# QCopter.net
KiCad netlist of a schematic drawn in EAGLE
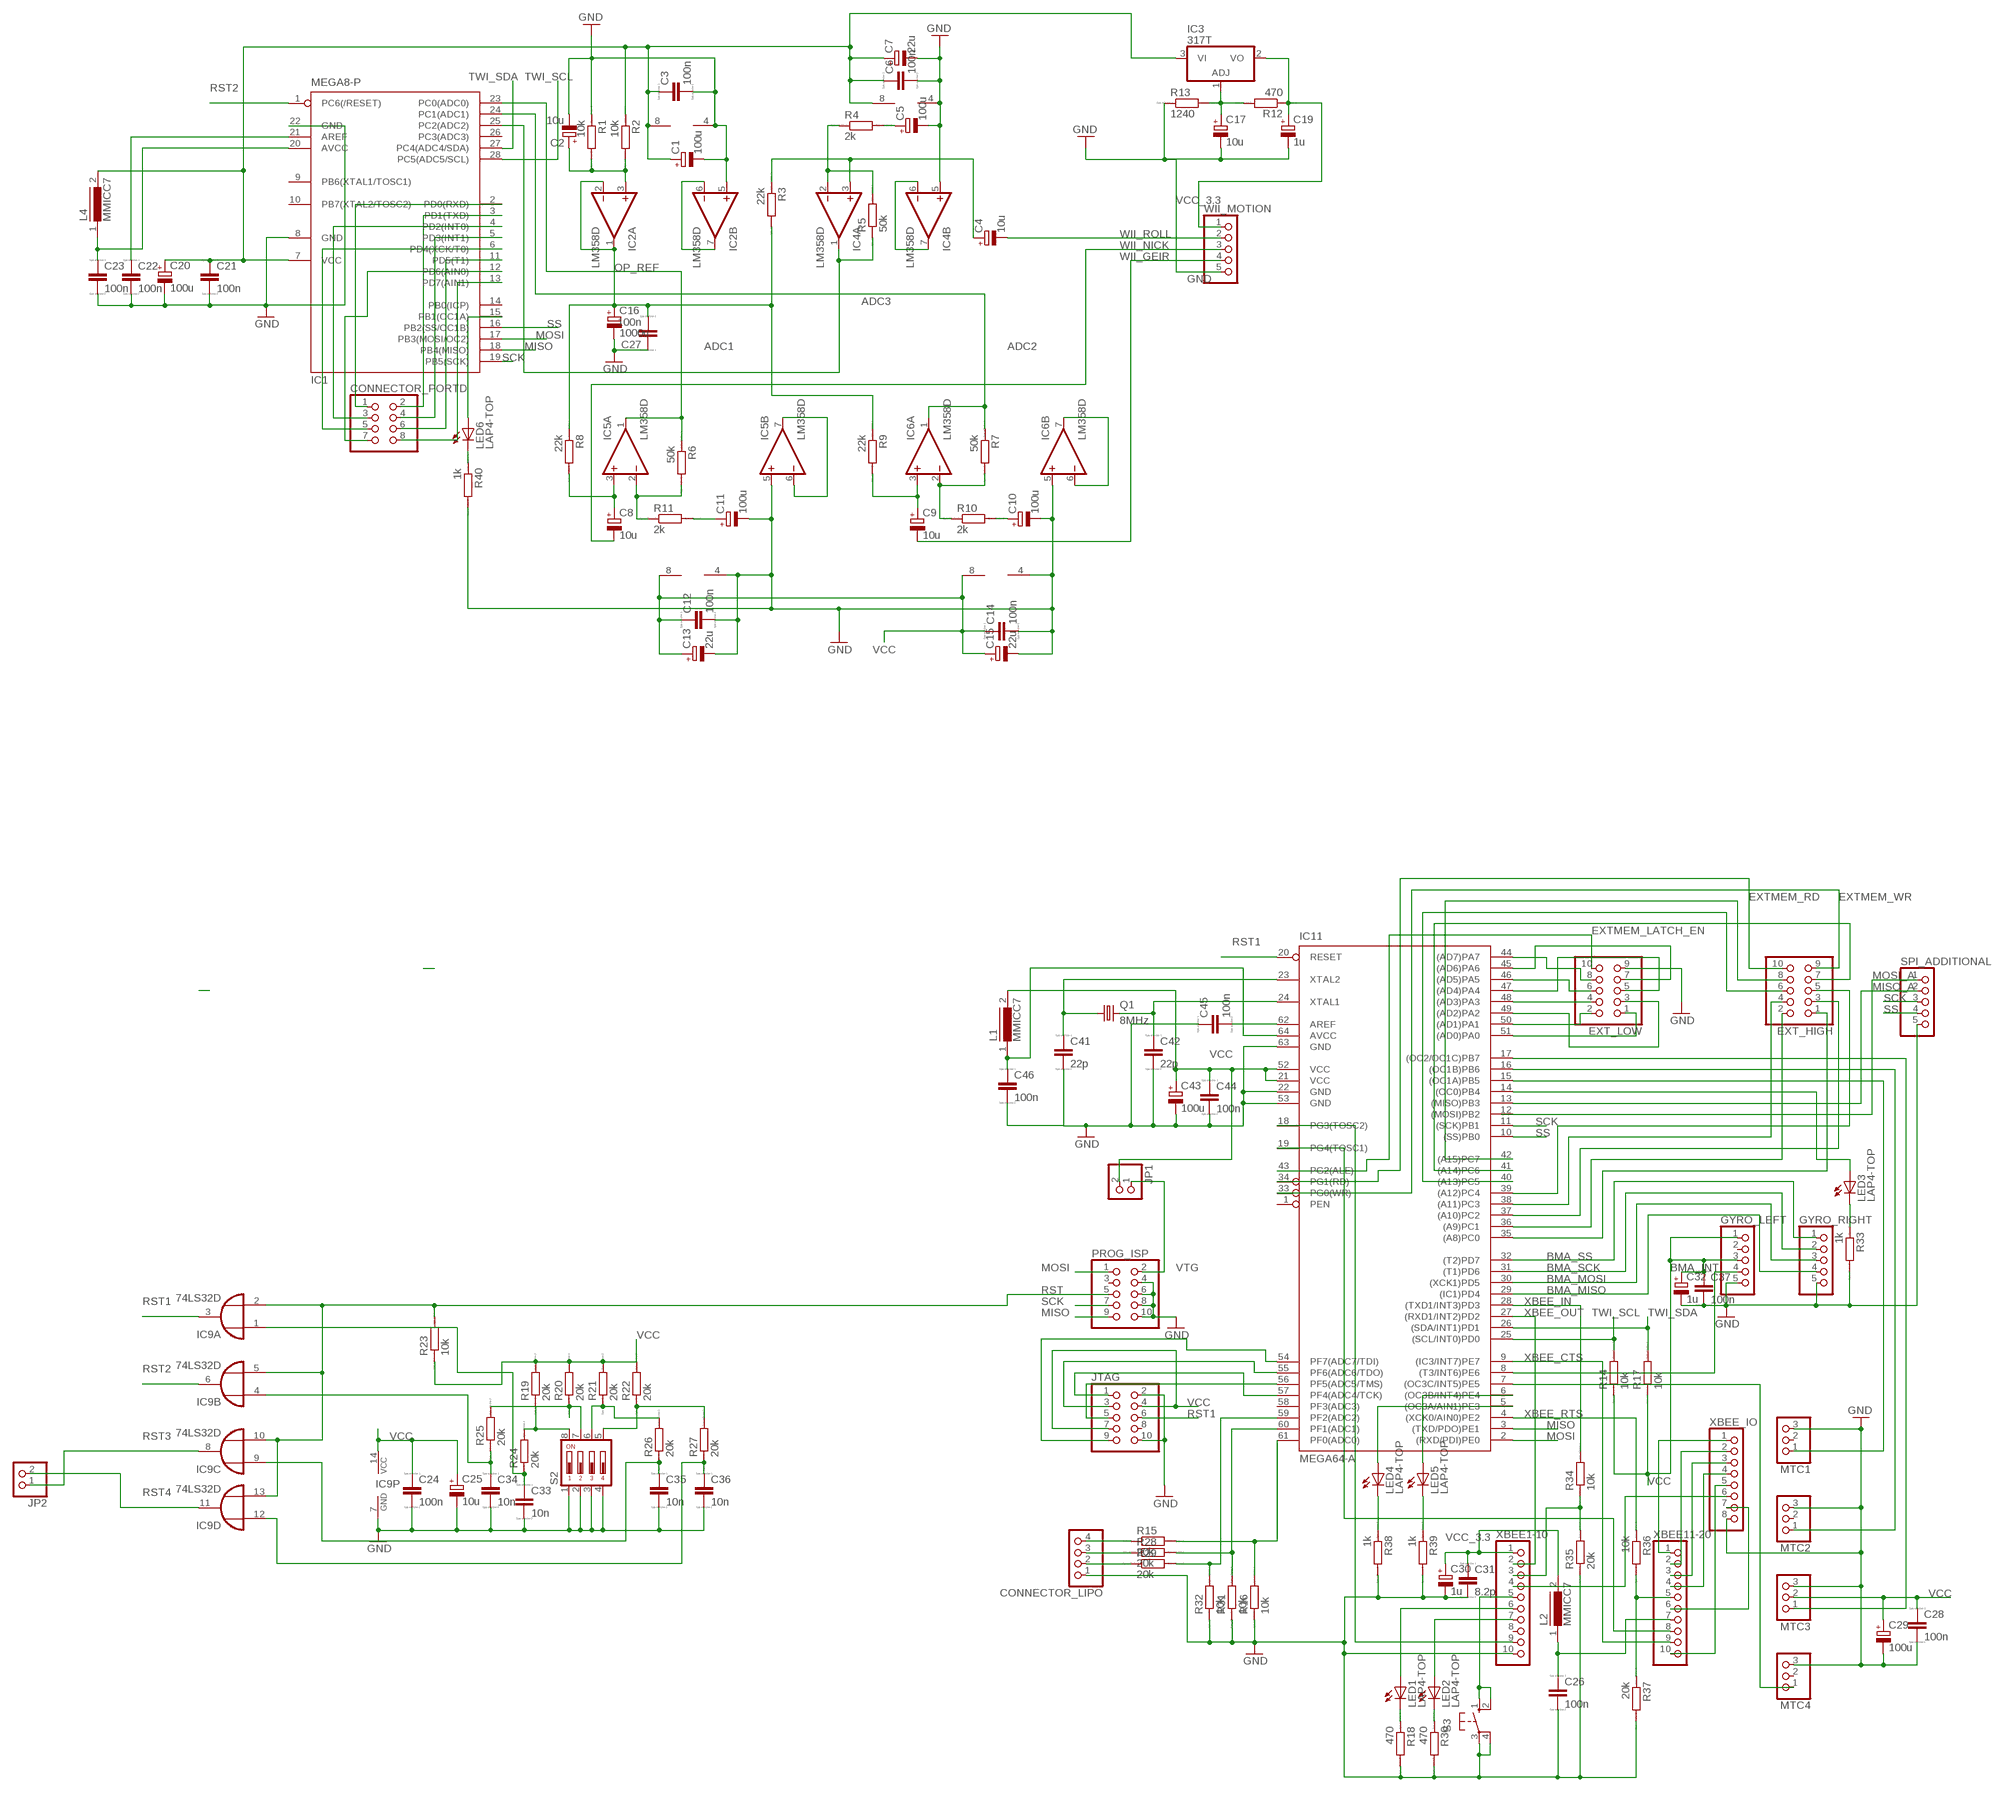
[diagram p0: schematic, sheet 1]

(export (version "E")
  (design (tool "Eeschema 10.0.6"))
  (components
    (comp (ref "C1")
      (value "100u")
      (footprint "eagle-import:153CLV-0505")
      (libsource (lib "eagle-import") (part "CPOL-EU153CLV-0505"))
    )
    (comp (ref "C2")
      (value "10u")
      (footprint "eagle-import:153CLV-0505")
      (libsource (lib "eagle-import") (part "CPOL-EU153CLV-0505"))
    )
    (comp (ref "C3")
      (value "100n")
      (footprint "eagle-import:C0805K")
      (libsource (lib "eagle-import") (part "C-EUC0805K"))
    )
    (comp (ref "C4")
      (value "10u")
      (footprint "eagle-import:153CLV-0505")
      (libsource (lib "eagle-import") (part "CPOL-EU153CLV-0505"))
    )
    (comp (ref "C5")
      (value "100u")
      (footprint "eagle-import:153CLV-0505")
      (libsource (lib "eagle-import") (part "CPOL-EU153CLV-0505"))
    )
    (comp (ref "C6")
      (value "100n")
      (footprint "eagle-import:C0805K")
      (libsource (lib "eagle-import") (part "C-EUC0805K"))
    )
    (comp (ref "C7")
      (value "22u")
      (footprint "eagle-import:153CLV-0505")
      (libsource (lib "eagle-import") (part "CPOL-EU153CLV-0505"))
    )
    (comp (ref "C8")
      (value "10u")
      (footprint "eagle-import:153CLV-0505")
      (libsource (lib "eagle-import") (part "CPOL-EU153CLV-0505"))
    )
    (comp (ref "C9")
      (value "10u")
      (footprint "eagle-import:153CLV-0505")
      (libsource (lib "eagle-import") (part "CPOL-EU153CLV-0505"))
    )
    (comp (ref "C10")
      (value "100u")
      (footprint "eagle-import:153CLV-0505")
      (libsource (lib "eagle-import") (part "CPOL-EU153CLV-0505"))
    )
    (comp (ref "C11")
      (value "100u")
      (footprint "eagle-import:153CLV-0505")
      (libsource (lib "eagle-import") (part "CPOL-EU153CLV-0505"))
    )
    (comp (ref "C12")
      (value "100n")
      (footprint "eagle-import:C0805K")
      (libsource (lib "eagle-import") (part "C-EUC0805K"))
    )
    (comp (ref "C13")
      (value "22u")
      (footprint "eagle-import:153CLV-0505")
      (libsource (lib "eagle-import") (part "CPOL-EU153CLV-0505"))
    )
    (comp (ref "C14")
      (value "100n")
      (footprint "eagle-import:C0805K")
      (libsource (lib "eagle-import") (part "C-EUC0805K"))
    )
    (comp (ref "C15")
      (value "22u")
      (footprint "eagle-import:153CLV-0505")
      (libsource (lib "eagle-import") (part "CPOL-EU153CLV-0505"))
    )
    (comp (ref "C16")
      (value "1000u")
      (footprint "eagle-import:E3,5-10")
      (libsource (lib "eagle-import") (part "CPOL-EUE3.5-10"))
    )
    (comp (ref "C17")
      (value "10u")
      (footprint "eagle-import:E5-6")
      (libsource (lib "eagle-import") (part "CPOL-EUE5-6"))
    )
    (comp (ref "C19")
      (value "1u")
      (footprint "eagle-import:E5-6")
      (libsource (lib "eagle-import") (part "CPOL-EUE5-6"))
    )
    (comp (ref "C20")
      (value "100u")
      (footprint "eagle-import:E5-6")
      (libsource (lib "eagle-import") (part "CPOL-EUE5-6"))
    )
    (comp (ref "C21")
      (value "100n")
      (footprint "eagle-import:C025-025X050")
      (libsource (lib "eagle-import") (part "C-EU025-025X050"))
    )
    (comp (ref "C22")
      (value "100n")
      (footprint "eagle-import:C025-025X050")
      (libsource (lib "eagle-import") (part "C-EU025-025X050"))
    )
    (comp (ref "C23")
      (value "100n")
      (footprint "eagle-import:C025-025X050")
      (libsource (lib "eagle-import") (part "C-EU025-025X050"))
    )
    (comp (ref "C24")
      (value "100n")
      (footprint "eagle-import:C0805K")
      (libsource (lib "eagle-import") (part "C-EUC0805K"))
    )
    (comp (ref "C25")
      (value "10u")
      (footprint "eagle-import:153CLV-0505")
      (libsource (lib "eagle-import") (part "CPOL-EU153CLV-0505"))
    )
    (comp (ref "C26")
      (value "100n")
      (footprint "eagle-import:C0805K")
      (libsource (lib "eagle-import") (part "C-EUC0805K"))
    )
    (comp (ref "C27")
      (value "100n")
      (footprint "eagle-import:C0805K")
      (libsource (lib "eagle-import") (part "C-EUC0805K"))
    )
    (comp (ref "C28")
      (value "100n")
      (footprint "eagle-import:C0805K")
      (libsource (lib "eagle-import") (part "C-EUC0805K"))
    )
    (comp (ref "C29")
      (value "100u")
      (footprint "eagle-import:153CLV-0605")
      (libsource (lib "eagle-import") (part "CPOL-EU153CLV-0605"))
    )
    (comp (ref "C30")
      (value "1u")
      (footprint "eagle-import:153CLV-0605")
      (libsource (lib "eagle-import") (part "CPOL-EU153CLV-0605"))
    )
    (comp (ref "C31")
      (value "8.2p")
      (footprint "eagle-import:C025-024X044")
      (libsource (lib "eagle-import") (part "C-EU025-024X044"))
    )
    (comp (ref "C32")
      (value "1u")
      (footprint "eagle-import:153CLV-0605")
      (libsource (lib "eagle-import") (part "CPOL-EU153CLV-0605"))
    )
    (comp (ref "C33")
      (value "10n")
      (footprint "eagle-import:C0805K")
      (libsource (lib "eagle-import") (part "C-EUC0805K"))
    )
    (comp (ref "C34")
      (value "10n")
      (footprint "eagle-import:C0805K")
      (libsource (lib "eagle-import") (part "C-EUC0805K"))
    )
    (comp (ref "C35")
      (value "10n")
      (footprint "eagle-import:C0805K")
      (libsource (lib "eagle-import") (part "C-EUC0805K"))
    )
    (comp (ref "C36")
      (value "10n")
      (footprint "eagle-import:C0805K")
      (libsource (lib "eagle-import") (part "C-EUC0805K"))
    )
    (comp (ref "C37")
      (value "100n")
      (footprint "eagle-import:C0805K")
      (libsource (lib "eagle-import") (part "C-EUC0805K"))
    )
    (comp (ref "C41")
      (value "22p")
      (footprint "eagle-import:C025-025X050")
      (libsource (lib "eagle-import") (part "C-EU025-025X050"))
    )
    (comp (ref "C42")
      (value "22p")
      (footprint "eagle-import:C025-025X050")
      (libsource (lib "eagle-import") (part "C-EU025-025X050"))
    )
    (comp (ref "C43")
      (value "100u")
      (footprint "eagle-import:153CLV-0605")
      (libsource (lib "eagle-import") (part "CPOL-EU153CLV-0605"))
    )
    (comp (ref "C44")
      (value "100n")
      (footprint "eagle-import:C0805K")
      (libsource (lib "eagle-import") (part "C-EUC0805K"))
    )
    (comp (ref "C45")
      (value "100n")
      (footprint "eagle-import:C0805K")
      (libsource (lib "eagle-import") (part "C-EUC0805K"))
    )
    (comp (ref "C46")
      (value "100n")
      (footprint "eagle-import:C0805K")
      (libsource (lib "eagle-import") (part "C-EUC0805K"))
    )
    (comp (ref "CONNECTOR_LIPO")
      (value "PINHD-1X4")
      (footprint "eagle-import:1X04")
      (libsource (lib "eagle-import") (part "PINHD-1X4"))
    )
    (comp (ref "CONNECTOR_PORTD")
      (value "PINHD-2X4")
      (footprint "eagle-import:2X04")
      (libsource (lib "eagle-import") (part "PINHD-2X4"))
    )
    (comp (ref "EXT_HIGH")
      (value "PINHD-2X5")
      (footprint "eagle-import:2X05")
      (libsource (lib "eagle-import") (part "PINHD-2X5"))
    )
    (comp (ref "EXT_LOW")
      (value "PINHD-2X5")
      (footprint "eagle-import:2X05")
      (libsource (lib "eagle-import") (part "PINHD-2X5"))
    )
    (comp (ref "GYRO_LEFT")
      (value "PINHD-1X5")
      (footprint "eagle-import:1X05")
      (libsource (lib "eagle-import") (part "PINHD-1X5"))
    )
    (comp (ref "GYRO_RIGHT")
      (value "PINHD-1X5")
      (footprint "eagle-import:1X05")
      (libsource (lib "eagle-import") (part "PINHD-1X5"))
    )
    (comp (ref "IC1")
      (value "MEGA8-P")
      (footprint "eagle-import:DIL28-3")
      (libsource (lib "eagle-import") (part "MEGA8-P"))
    )
    (comp (ref "IC2")
      (value "LM358D")
      (footprint "eagle-import:SO08")
      (libsource (lib "eagle-import") (part "LM358D"))
    )
    (comp (ref "IC3")
      (value "317T")
      (footprint "eagle-import:TO220H")
      (libsource (lib "eagle-import") (part "317T"))
    )
    (comp (ref "IC4")
      (value "LM358D")
      (footprint "eagle-import:SO08")
      (libsource (lib "eagle-import") (part "LM358D"))
    )
    (comp (ref "IC5")
      (value "LM358D")
      (footprint "eagle-import:SO08")
      (libsource (lib "eagle-import") (part "LM358D"))
    )
    (comp (ref "IC6")
      (value "LM358D")
      (footprint "eagle-import:SO08")
      (libsource (lib "eagle-import") (part "LM358D"))
    )
    (comp (ref "IC9")
      (value "74LS32D")
      (footprint "eagle-import:SO14")
      (libsource (lib "eagle-import") (part "7432DLS"))
    )
    (comp (ref "IC11")
      (value "MEGA64-A")
      (footprint "eagle-import:TQFP64")
      (fields (field (name "MPN") "ATMEGA64-16AU"))
      (libsource (lib "eagle-import") (part "MEGA64-A"))
    )
    (comp (ref "JP1")
      (value "PINHD-1X2")
      (footprint "eagle-import:1X02")
      (libsource (lib "eagle-import") (part "PINHD-1X2"))
    )
    (comp (ref "JP2")
      (value "PINHD-1X2")
      (footprint "eagle-import:1X02")
      (libsource (lib "eagle-import") (part "PINHD-1X2"))
    )
    (comp (ref "JTAG")
      (value "PINHD-2X5")
      (footprint "eagle-import:2X05")
      (libsource (lib "eagle-import") (part "PINHD-2X5"))
    )
    (comp (ref "L1")
      (value "MMICC7")
      (footprint "eagle-import:MMICC7")
      (libsource (lib "eagle-import") (part "MMICC7"))
    )
    (comp (ref "L2")
      (value "MMICC7")
      (footprint "eagle-import:MMICC7")
      (libsource (lib "eagle-import") (part "MMICC7"))
    )
    (comp (ref "L4")
      (value "MMICC7")
      (footprint "eagle-import:MMICC7")
      (libsource (lib "eagle-import") (part "MMICC7"))
    )
    (comp (ref "LED1")
      (value "LAP4-TOP")
      (footprint "eagle-import:P47F-TOP")
      (libsource (lib "eagle-import") (part "P4-TOPLA"))
    )
    (comp (ref "LED2")
      (value "LAP4-TOP")
      (footprint "eagle-import:P47F-TOP")
      (libsource (lib "eagle-import") (part "P4-TOPLA"))
    )
    (comp (ref "LED3")
      (value "LAP4-TOP")
      (footprint "eagle-import:P47F-TOP")
      (libsource (lib "eagle-import") (part "P4-TOPLA"))
    )
    (comp (ref "LED4")
      (value "LAP4-TOP")
      (footprint "eagle-import:P47F-TOP")
      (libsource (lib "eagle-import") (part "P4-TOPLA"))
    )
    (comp (ref "LED5")
      (value "LAP4-TOP")
      (footprint "eagle-import:P47F-TOP")
      (libsource (lib "eagle-import") (part "P4-TOPLA"))
    )
    (comp (ref "LED6")
      (value "LAP4-TOP")
      (footprint "eagle-import:P47F-TOP")
      (libsource (lib "eagle-import") (part "P4-TOPLA"))
    )
    (comp (ref "MTC1")
      (value "PINHD-1X3")
      (footprint "eagle-import:1X03")
      (libsource (lib "eagle-import") (part "PINHD-1X3"))
    )
    (comp (ref "MTC2")
      (value "PINHD-1X3")
      (footprint "eagle-import:1X03")
      (libsource (lib "eagle-import") (part "PINHD-1X3"))
    )
    (comp (ref "MTC3")
      (value "PINHD-1X3")
      (footprint "eagle-import:1X03")
      (libsource (lib "eagle-import") (part "PINHD-1X3"))
    )
    (comp (ref "MTC4")
      (value "PINHD-1X3")
      (footprint "eagle-import:1X03")
      (libsource (lib "eagle-import") (part "PINHD-1X3"))
    )
    (comp (ref "PROG_ISP")
      (value "PINHD-2X5")
      (footprint "eagle-import:2X05")
      (libsource (lib "eagle-import") (part "PINHD-2X5"))
    )
    (comp (ref "Q1")
      (value "8MHz")
      (footprint "eagle-import:HC49_S")
      (libsource (lib "eagle-import") (part "CRYSTALHC49S"))
    )
    (comp (ref "R1")
      (value "10k")
      (footprint "eagle-import:R1206")
      (libsource (lib "eagle-import") (part "R-EU_R1206"))
    )
    (comp (ref "R2")
      (value "10k")
      (footprint "eagle-import:R1206")
      (libsource (lib "eagle-import") (part "R-EU_R1206"))
    )
    (comp (ref "R3")
      (value "22k")
      (footprint "eagle-import:R1206")
      (libsource (lib "eagle-import") (part "R-EU_R1206"))
    )
    (comp (ref "R4")
      (value "2k")
      (footprint "eagle-import:R1206")
      (libsource (lib "eagle-import") (part "R-EU_R1206"))
    )
    (comp (ref "R5")
      (value "50k")
      (footprint "eagle-import:R1206")
      (libsource (lib "eagle-import") (part "R-EU_R1206"))
    )
    (comp (ref "R6")
      (value "50k")
      (footprint "eagle-import:R1206")
      (libsource (lib "eagle-import") (part "R-EU_R1206"))
    )
    (comp (ref "R7")
      (value "50k")
      (footprint "eagle-import:R1206")
      (libsource (lib "eagle-import") (part "R-EU_R1206"))
    )
    (comp (ref "R8")
      (value "22k")
      (footprint "eagle-import:R1206")
      (libsource (lib "eagle-import") (part "R-EU_R1206"))
    )
    (comp (ref "R9")
      (value "22k")
      (footprint "eagle-import:R1206")
      (libsource (lib "eagle-import") (part "R-EU_R1206"))
    )
    (comp (ref "R10")
      (value "2k")
      (footprint "eagle-import:R1206")
      (libsource (lib "eagle-import") (part "R-EU_R1206"))
    )
    (comp (ref "R11")
      (value "2k")
      (footprint "eagle-import:R1206")
      (libsource (lib "eagle-import") (part "R-EU_R1206"))
    )
    (comp (ref "R12")
      (value "470")
      (footprint "eagle-import:0414_15")
      (libsource (lib "eagle-import") (part "R-EU_0414_15"))
    )
    (comp (ref "R13")
      (value "1240")
      (footprint "eagle-import:0414_15")
      (libsource (lib "eagle-import") (part "R-EU_0414_15"))
    )
    (comp (ref "R14")
      (value "10k")
      (footprint "eagle-import:R1206")
      (libsource (lib "eagle-import") (part "R-EU_R1206"))
    )
    (comp (ref "R15")
      (value "20k")
      (footprint "eagle-import:R1206")
      (libsource (lib "eagle-import") (part "R-EU_R1206"))
    )
    (comp (ref "R16")
      (value "10k")
      (footprint "eagle-import:R1206")
      (libsource (lib "eagle-import") (part "R-EU_R1206"))
    )
    (comp (ref "R17")
      (value "10k")
      (footprint "eagle-import:R1206")
      (libsource (lib "eagle-import") (part "R-EU_R1206"))
    )
    (comp (ref "R18")
      (value "470")
      (footprint "eagle-import:R1206")
      (libsource (lib "eagle-import") (part "R-EU_R1206"))
    )
    (comp (ref "R19")
      (value "20k")
      (footprint "eagle-import:R1206")
      (libsource (lib "eagle-import") (part "R-EU_R1206"))
    )
    (comp (ref "R20")
      (value "20k")
      (footprint "eagle-import:R1206")
      (libsource (lib "eagle-import") (part "R-EU_R1206"))
    )
    (comp (ref "R21")
      (value "20k")
      (footprint "eagle-import:R1206")
      (libsource (lib "eagle-import") (part "R-EU_R1206"))
    )
    (comp (ref "R22")
      (value "20k")
      (footprint "eagle-import:R1206")
      (libsource (lib "eagle-import") (part "R-EU_R1206"))
    )
    (comp (ref "R23")
      (value "10k")
      (footprint "eagle-import:R1206")
      (libsource (lib "eagle-import") (part "R-EU_R1206"))
    )
    (comp (ref "R24")
      (value "20k")
      (footprint "eagle-import:R1206")
      (libsource (lib "eagle-import") (part "R-EU_R1206"))
    )
    (comp (ref "R25")
      (value "20k")
      (footprint "eagle-import:R1206")
      (libsource (lib "eagle-import") (part "R-EU_R1206"))
    )
    (comp (ref "R26")
      (value "20k")
      (footprint "eagle-import:R1206")
      (libsource (lib "eagle-import") (part "R-EU_R1206"))
    )
    (comp (ref "R27")
      (value "20k")
      (footprint "eagle-import:R1206W")
      (libsource (lib "eagle-import") (part "R-EU_R1206W"))
    )
    (comp (ref "R28")
      (value "20k")
      (footprint "eagle-import:R1206")
      (libsource (lib "eagle-import") (part "R-EU_R1206"))
    )
    (comp (ref "R29")
      (value "20k")
      (footprint "eagle-import:R1206")
      (libsource (lib "eagle-import") (part "R-EU_R1206"))
    )
    (comp (ref "R30")
      (value "470")
      (footprint "eagle-import:R1206")
      (libsource (lib "eagle-import") (part "R-EU_R1206"))
    )
    (comp (ref "R31")
      (value "10k")
      (footprint "eagle-import:R1206")
      (libsource (lib "eagle-import") (part "R-EU_R1206"))
    )
    (comp (ref "R32")
      (value "10k")
      (footprint "eagle-import:R1206")
      (libsource (lib "eagle-import") (part "R-EU_R1206"))
    )
    (comp (ref "R33")
      (value "1k")
      (footprint "eagle-import:R1206")
      (libsource (lib "eagle-import") (part "R-EU_R1206"))
    )
    (comp (ref "R34")
      (value "10k")
      (footprint "eagle-import:R1206")
      (libsource (lib "eagle-import") (part "R-EU_R1206"))
    )
    (comp (ref "R35")
      (value "20k")
      (footprint "eagle-import:R1206")
      (libsource (lib "eagle-import") (part "R-EU_R1206"))
    )
    (comp (ref "R36")
      (value "10k")
      (footprint "eagle-import:R1206")
      (libsource (lib "eagle-import") (part "R-EU_R1206"))
    )
    (comp (ref "R37")
      (value "20k")
      (footprint "eagle-import:R1206")
      (libsource (lib "eagle-import") (part "R-EU_R1206"))
    )
    (comp (ref "R38")
      (value "1k")
      (footprint "eagle-import:R1206")
      (libsource (lib "eagle-import") (part "R-EU_R1206"))
    )
    (comp (ref "R39")
      (value "1k")
      (footprint "eagle-import:R1206")
      (libsource (lib "eagle-import") (part "R-EU_R1206"))
    )
    (comp (ref "R40")
      (value "1k")
      (footprint "eagle-import:R1206")
      (libsource (lib "eagle-import") (part "R-EU_R1206"))
    )
    (comp (ref "S2")
      (value "DS04")
      (footprint "eagle-import:DS-04")
      (libsource (lib "eagle-import") (part "DS04"))
    )
    (comp (ref "S3")
      (value "10-XX")
      (footprint "eagle-import:B3F-10XX")
      (fields (field (name "MPN") "B3F-1000"))
      (libsource (lib "eagle-import") (part "10-XX"))
    )
    (comp (ref "SPI_ADDITIONAL")
      (value "PINHD-1X5")
      (footprint "eagle-import:1X05")
      (libsource (lib "eagle-import") (part "PINHD-1X5"))
    )
    (comp (ref "WII_MOTION")
      (value "PINHD-1X5")
      (footprint "eagle-import:1X05")
      (libsource (lib "eagle-import") (part "PINHD-1X5"))
    )
    (comp (ref "XBEE1-10")
      (value "PINHD-1X10M")
      (footprint "eagle-import:1X10M")
      (libsource (lib "eagle-import") (part "PINHD-1X10M"))
    )
    (comp (ref "XBEE11-20")
      (value "PINHD-1X10M")
      (footprint "eagle-import:1X10M")
      (libsource (lib "eagle-import") (part "PINHD-1X10M"))
    )
    (comp (ref "XBEE_IO")
      (value "PINHD-1X8")
      (footprint "eagle-import:1X08")
      (libsource (lib "eagle-import") (part "PINHD-1X8"))
    )
  )
  (nets
    (net (code "1") (name "/ADC1") (class "Default")
      (node (ref "IC1") (pin "23") (pinfunction "PC0(ADC0)_23") (pintype "bidirectional"))
      (node (ref "IC5") (pin "1") (pinfunction "OUT_1") (pintype "output"))
      (node (ref "R6") (pin "1") (pinfunction "1_1") (pintype "passive"))
    )
    (net (code "2") (name "/ADC2") (class "Default")
      (node (ref "IC1") (pin "24") (pinfunction "PC1(ADC1)_24") (pintype "bidirectional"))
      (node (ref "IC6") (pin "1") (pinfunction "OUT_1") (pintype "output"))
      (node (ref "R7") (pin "1") (pinfunction "1_1") (pintype "passive"))
    )
    (net (code "3") (name "/ADC3") (class "Default")
      (node (ref "IC1") (pin "25") (pinfunction "PC2(ADC2)_25") (pintype "bidirectional"))
      (node (ref "IC4") (pin "1") (pinfunction "OUT_1") (pintype "output"))
      (node (ref "R5") (pin "1") (pinfunction "1_1") (pintype "passive"))
    )
    (net (code "4") (name "/BMA_INT") (class "Default")
      (node (ref "GYRO_LEFT") (pin "4") (pinfunction "4_4") (pintype "passive"))
      (node (ref "IC11") (pin "8") (pinfunction "(T3/INT6)PE6_8") (pintype "bidirectional"))
    )
    (net (code "5") (name "/BMA_MISO") (class "Default")
      (node (ref "GYRO_RIGHT") (pin "4") (pinfunction "4_4") (pintype "passive"))
      (node (ref "IC11") (pin "29") (pinfunction "(IC1)PD4_29") (pintype "bidirectional"))
    )
    (net (code "6") (name "/BMA_MOSI") (class "Default")
      (node (ref "GYRO_RIGHT") (pin "3") (pinfunction "3_3") (pintype "passive"))
      (node (ref "IC11") (pin "30") (pinfunction "(XCK1)PD5_30") (pintype "bidirectional"))
    )
    (net (code "7") (name "/BMA_SCK") (class "Default")
      (node (ref "GYRO_RIGHT") (pin "2") (pinfunction "2_2") (pintype "passive"))
      (node (ref "IC11") (pin "31") (pinfunction "(T1)PD6_31") (pintype "bidirectional"))
    )
    (net (code "8") (name "/BMA_SS") (class "Default")
      (node (ref "GYRO_RIGHT") (pin "1") (pinfunction "1_1") (pintype "passive"))
      (node (ref "IC11") (pin "32") (pinfunction "(T2)PD7_32") (pintype "bidirectional"))
    )
    (net (code "9") (name "/EXTMEM_LATCH_EN") (class "Default")
      (node (ref "EXT_LOW") (pin "10") (pinfunction "10_10") (pintype "passive"))
      (node (ref "IC11") (pin "43") (pinfunction "PG2(ALE)_43") (pintype "bidirectional"))
    )
    (net (code "10") (name "/EXTMEM_RD") (class "Default")
      (node (ref "EXT_HIGH") (pin "10") (pinfunction "10_10") (pintype "passive"))
      (node (ref "IC11") (pin "34") (pinfunction "PG1(RD)_34") (pintype "bidirectional"))
    )
    (net (code "11") (name "/EXTMEM_WR") (class "Default")
      (node (ref "EXT_HIGH") (pin "9") (pinfunction "9_9") (pintype "passive"))
      (node (ref "IC11") (pin "33") (pinfunction "PG0(WR)_33") (pintype "bidirectional"))
    )
    (net (code "12") (name "/MISO") (class "Default")
      (node (ref "IC1") (pin "18") (pinfunction "PB4(MISO)_18") (pintype "bidirectional"))
      (node (ref "IC11") (pin "3") (pinfunction "(TXD/PDO)PE1_3") (pintype "bidirectional"))
      (node (ref "PROG_ISP") (pin "9") (pinfunction "9_9") (pintype "passive"))
    )
    (net (code "13") (name "/MISO_A") (class "Default")
      (node (ref "IC11") (pin "13") (pinfunction "(MISO)PB3_13") (pintype "bidirectional"))
      (node (ref "SPI_ADDITIONAL") (pin "2") (pinfunction "2_2") (pintype "passive"))
    )
    (net (code "14") (name "/MOSI") (class "Default")
      (node (ref "IC1") (pin "17") (pinfunction "PB3(MOSI/OC2)_17") (pintype "bidirectional"))
      (node (ref "IC11") (pin "2") (pinfunction "(RXD/PDI)PE0_2") (pintype "bidirectional"))
      (node (ref "PROG_ISP") (pin "1") (pinfunction "1_1") (pintype "passive"))
    )
    (net (code "15") (name "/MOSI_A") (class "Default")
      (node (ref "SPI_ADDITIONAL") (pin "1") (pinfunction "1_1") (pintype "passive"))
    )
    (net (code "16") (name "/OP_REF") (class "Default")
      (node (ref "C16") (pin "+") (pinfunction "+_+") (pintype "passive"))
      (node (ref "C27") (pin "2") (pinfunction "2_2") (pintype "passive"))
      (node (ref "IC2") (pin "1") (pinfunction "OUT_1") (pintype "output"))
      (node (ref "IC2") (pin "2") (pinfunction "-IN_2") (pintype "input"))
      (node (ref "R3") (pin "2") (pinfunction "2_2") (pintype "passive"))
      (node (ref "R8") (pin "1") (pinfunction "1_1") (pintype "passive"))
      (node (ref "R9") (pin "1") (pinfunction "1_1") (pintype "passive"))
    )
    (net (code "17") (name "/RST") (class "Default")
      (node (ref "IC9") (pin "10") (pinfunction "I1_10") (pintype "input"))
      (node (ref "IC9") (pin "13") (pinfunction "I1_13") (pintype "input"))
      (node (ref "IC9") (pin "2") (pinfunction "I1_2") (pintype "input"))
      (node (ref "IC9") (pin "5") (pinfunction "I1_5") (pintype "input"))
      (node (ref "PROG_ISP") (pin "5") (pinfunction "5_5") (pintype "passive"))
      (node (ref "R23") (pin "2") (pinfunction "2_2") (pintype "passive"))
    )
    (net (code "18") (name "/RST1") (class "Default")
      (node (ref "IC11") (pin "20") (pinfunction "RESET_20") (pintype "input"))
      (node (ref "IC9") (pin "3") (pinfunction "O_3") (pintype "output"))
      (node (ref "JTAG") (pin "6") (pinfunction "6_6") (pintype "passive"))
    )
    (net (code "19") (name "/RST2") (class "Default")
      (node (ref "IC1") (pin "1") (pinfunction "PC6(/RESET)_1") (pintype "bidirectional"))
      (node (ref "IC9") (pin "6") (pinfunction "O_6") (pintype "output"))
    )
    (net (code "20") (name "/RST3") (class "Default")
      (node (ref "IC9") (pin "8") (pinfunction "O_8") (pintype "output"))
      (node (ref "JP2") (pin "1") (pinfunction "1_1") (pintype "passive"))
    )
    (net (code "21") (name "/RST4") (class "Default")
      (node (ref "IC9") (pin "11") (pinfunction "O_11") (pintype "output"))
      (node (ref "JP2") (pin "2") (pinfunction "2_2") (pintype "passive"))
    )
    (net (code "22") (name "/SCK") (class "Default")
      (node (ref "IC1") (pin "19") (pinfunction "PB5(SCK)_19") (pintype "bidirectional"))
      (node (ref "IC11") (pin "11") (pinfunction "(SCK)PB1_11") (pintype "bidirectional"))
      (node (ref "PROG_ISP") (pin "7") (pinfunction "7_7") (pintype "passive"))
      (node (ref "SPI_ADDITIONAL") (pin "3") (pinfunction "3_3") (pintype "passive"))
    )
    (net (code "23") (name "/SS") (class "Default")
      (node (ref "IC1") (pin "16") (pinfunction "PB2(SS/OC1B)_16") (pintype "bidirectional"))
      (node (ref "IC11") (pin "10") (pinfunction "(SS)PB0_10") (pintype "bidirectional"))
      (node (ref "SPI_ADDITIONAL") (pin "4") (pinfunction "4_4") (pintype "passive"))
    )
    (net (code "24") (name "/TWI_SCL") (class "Default")
      (node (ref "IC1") (pin "28") (pinfunction "PC5(ADC5/SCL)_28") (pintype "bidirectional"))
      (node (ref "IC11") (pin "25") (pinfunction "(SCL/INT0)PD0_25") (pintype "bidirectional"))
      (node (ref "R14") (pin "2") (pinfunction "2_2") (pintype "passive"))
    )
    (net (code "25") (name "/TWI_SDA") (class "Default")
      (node (ref "IC1") (pin "27") (pinfunction "PC4(ADC4/SDA)_27") (pintype "bidirectional"))
      (node (ref "IC11") (pin "26") (pinfunction "(SDA/INT1)PD1_26") (pintype "bidirectional"))
      (node (ref "R17") (pin "2") (pinfunction "2_2") (pintype "passive"))
    )
    (net (code "26") (name "/VCC") (class "Default")
      (node (ref "C1") (pin "+") (pinfunction "+_+") (pintype "passive"))
      (node (ref "C12") (pin "1") (pinfunction "1_1") (pintype "passive"))
      (node (ref "C13") (pin "+") (pinfunction "+_+") (pintype "passive"))
      (node (ref "C14") (pin "1") (pinfunction "1_1") (pintype "passive"))
      (node (ref "C15") (pin "+") (pinfunction "+_+") (pintype "passive"))
      (node (ref "C20") (pin "+") (pinfunction "+_+") (pintype "passive"))
      (node (ref "C21") (pin "1") (pinfunction "1_1") (pintype "passive"))
      (node (ref "C24") (pin "1") (pinfunction "1_1") (pintype "passive"))
      (node (ref "C25") (pin "+") (pinfunction "+_+") (pintype "passive"))
      (node (ref "C28") (pin "1") (pinfunction "1_1") (pintype "passive"))
      (node (ref "C29") (pin "+") (pinfunction "+_+") (pintype "passive"))
      (node (ref "C3") (pin "1") (pinfunction "1_1") (pintype "passive"))
      (node (ref "C32") (pin "+") (pinfunction "+_+") (pintype "passive"))
      (node (ref "C37") (pin "1") (pinfunction "1_1") (pintype "passive"))
      (node (ref "C43") (pin "+") (pinfunction "+_+") (pintype "passive"))
      (node (ref "C44") (pin "1") (pinfunction "1_1") (pintype "passive"))
      (node (ref "C6") (pin "1") (pinfunction "1_1") (pintype "passive"))
      (node (ref "C7") (pin "+") (pinfunction "+_+") (pintype "passive"))
      (node (ref "GYRO_LEFT") (pin "1") (pinfunction "1_1") (pintype "passive"))
      (node (ref "GYRO_LEFT") (pin "3") (pinfunction "3_3") (pintype "passive"))
      (node (ref "IC1") (pin "7") (pinfunction "VCC_7") (pintype "power_in"))
      (node (ref "IC11") (pin "21") (pinfunction "VCC_21") (pintype "power_in"))
      (node (ref "IC11") (pin "52") (pinfunction "VCC_52") (pintype "power_in"))
      (node (ref "IC2") (pin "8") (pinfunction "V+_8") (pintype "power_in"))
      (node (ref "IC3") (pin "3") (pinfunction "VI_3") (pintype "input"))
      (node (ref "IC4") (pin "8") (pinfunction "V+_8") (pintype "power_in"))
      (node (ref "IC5") (pin "8") (pinfunction "V+_8") (pintype "power_in"))
      (node (ref "IC6") (pin "8") (pinfunction "V+_8") (pintype "power_in"))
      (node (ref "IC9") (pin "14") (pinfunction "VCC_14") (pintype "power_in"))
      (node (ref "JP1") (pin "2") (pinfunction "2_2") (pintype "passive"))
      (node (ref "JTAG") (pin "4") (pinfunction "4_4") (pintype "passive"))
      (node (ref "JTAG") (pin "7") (pinfunction "7_7") (pintype "passive"))
      (node (ref "L1") (pin "2") (pinfunction "2_2") (pintype "passive"))
      (node (ref "L4") (pin "2") (pinfunction "2_2") (pintype "passive"))
      (node (ref "MTC3") (pin "2") (pinfunction "2_2") (pintype "passive"))
      (node (ref "R14") (pin "1") (pinfunction "1_1") (pintype "passive"))
      (node (ref "R17") (pin "1") (pinfunction "1_1") (pintype "passive"))
      (node (ref "R19") (pin "2") (pinfunction "2_2") (pintype "passive"))
      (node (ref "R2") (pin "1") (pinfunction "1_1") (pintype "passive"))
      (node (ref "R20") (pin "2") (pinfunction "2_2") (pintype "passive"))
      (node (ref "R21") (pin "2") (pinfunction "2_2") (pintype "passive"))
      (node (ref "R22") (pin "2") (pinfunction "2_2") (pintype "passive"))
      (node (ref "R23") (pin "1") (pinfunction "1_1") (pintype "passive"))
    )
    (net (code "27") (name "/VCC_3.3") (class "Default")
      (node (ref "C19") (pin "+") (pinfunction "+_+") (pintype "passive"))
      (node (ref "C30") (pin "+") (pinfunction "+_+") (pintype "passive"))
      (node (ref "C31") (pin "1") (pinfunction "1_1") (pintype "passive"))
      (node (ref "IC3") (pin "2") (pinfunction "VO_2") (pintype "passive"))
      (node (ref "L2") (pin "2") (pinfunction "2_2") (pintype "passive"))
      (node (ref "R12") (pin "1") (pinfunction "1_1") (pintype "passive"))
      (node (ref "WII_MOTION") (pin "1") (pinfunction "1_1") (pintype "passive"))
      (node (ref "XBEE1-10") (pin "1") (pinfunction "1_1") (pintype "passive"))
    )
    (net (code "28") (name "/VTG") (class "Default")
      (node (ref "JP1") (pin "1") (pinfunction "1_1") (pintype "passive"))
      (node (ref "PROG_ISP") (pin "2") (pinfunction "2_2") (pintype "passive"))
    )
    (net (code "29") (name "/WII_GEIR") (class "Default")
      (node (ref "C9") (pin "-") (pinfunction "-_-") (pintype "passive"))
      (node (ref "WII_MOTION") (pin "4") (pinfunction "4_4") (pintype "passive"))
    )
    (net (code "30") (name "/WII_NICK") (class "Default")
      (node (ref "C8") (pin "-") (pinfunction "-_-") (pintype "passive"))
      (node (ref "WII_MOTION") (pin "3") (pinfunction "3_3") (pintype "passive"))
    )
    (net (code "31") (name "/WII_ROLL") (class "Default")
      (node (ref "C4") (pin "-") (pinfunction "-_-") (pintype "passive"))
      (node (ref "WII_MOTION") (pin "2") (pinfunction "2_2") (pintype "passive"))
    )
    (net (code "32") (name "/XBEE_CTS") (class "Default")
      (node (ref "IC11") (pin "9") (pinfunction "(IC3/INT7)PE7_9") (pintype "bidirectional"))
      (node (ref "XBEE11-20") (pin "9") (pinfunction "9_9") (pintype "passive"))
    )
    (net (code "33") (name "/XBEE_IN") (class "Default")
      (node (ref "IC11") (pin "28") (pinfunction "(TXD1/INT3)PD3_28") (pintype "bidirectional"))
      (node (ref "R34") (pin "2") (pinfunction "2_2") (pintype "passive"))
    )
    (net (code "34") (name "/XBEE_OUT") (class "Default")
      (node (ref "IC11") (pin "27") (pinfunction "(RXD1/INT2)PD2_27") (pintype "bidirectional"))
      (node (ref "XBEE1-10") (pin "2") (pinfunction "2_2") (pintype "passive"))
    )
    (net (code "35") (name "/XBEE_RTS") (class "Default")
      (node (ref "IC11") (pin "4") (pinfunction "(XCK0/AIN0)PE2_4") (pintype "bidirectional"))
      (node (ref "R36") (pin "1") (pinfunction "1_1") (pintype "passive"))
    )
    (net (code "36") (name "GND") (class "Default")
      (node (ref "C1") (pin "-") (pinfunction "-_-") (pintype "passive"))
      (node (ref "C10") (pin "-") (pinfunction "-_-") (pintype "passive"))
      (node (ref "C11") (pin "-") (pinfunction "-_-") (pintype "passive"))
      (node (ref "C12") (pin "2") (pinfunction "2_2") (pintype "passive"))
      (node (ref "C13") (pin "-") (pinfunction "-_-") (pintype "passive"))
      (node (ref "C14") (pin "2") (pinfunction "2_2") (pintype "passive"))
      (node (ref "C15") (pin "-") (pinfunction "-_-") (pintype "passive"))
      (node (ref "C16") (pin "-") (pinfunction "-_-") (pintype "passive"))
      (node (ref "C17") (pin "-") (pinfunction "-_-") (pintype "passive"))
      (node (ref "C19") (pin "-") (pinfunction "-_-") (pintype "passive"))
      (node (ref "C2") (pin "-") (pinfunction "-_-") (pintype "passive"))
      (node (ref "C20") (pin "-") (pinfunction "-_-") (pintype "passive"))
      (node (ref "C21") (pin "2") (pinfunction "2_2") (pintype "passive"))
      (node (ref "C22") (pin "2") (pinfunction "2_2") (pintype "passive"))
      (node (ref "C23") (pin "2") (pinfunction "2_2") (pintype "passive"))
      (node (ref "C24") (pin "2") (pinfunction "2_2") (pintype "passive"))
      (node (ref "C25") (pin "-") (pinfunction "-_-") (pintype "passive"))
      (node (ref "C26") (pin "2") (pinfunction "2_2") (pintype "passive"))
      (node (ref "C27") (pin "1") (pinfunction "1_1") (pintype "passive"))
      (node (ref "C28") (pin "2") (pinfunction "2_2") (pintype "passive"))
      (node (ref "C29") (pin "-") (pinfunction "-_-") (pintype "passive"))
      (node (ref "C3") (pin "2") (pinfunction "2_2") (pintype "passive"))
      (node (ref "C30") (pin "-") (pinfunction "-_-") (pintype "passive"))
      (node (ref "C31") (pin "2") (pinfunction "2_2") (pintype "passive"))
      (node (ref "C32") (pin "-") (pinfunction "-_-") (pintype "passive"))
      (node (ref "C33") (pin "2") (pinfunction "2_2") (pintype "passive"))
      (node (ref "C34") (pin "2") (pinfunction "2_2") (pintype "passive"))
      (node (ref "C35") (pin "2") (pinfunction "2_2") (pintype "passive"))
      (node (ref "C36") (pin "2") (pinfunction "2_2") (pintype "passive"))
      (node (ref "C37") (pin "2") (pinfunction "2_2") (pintype "passive"))
      (node (ref "C41") (pin "2") (pinfunction "2_2") (pintype "passive"))
      (node (ref "C42") (pin "2") (pinfunction "2_2") (pintype "passive"))
      (node (ref "C43") (pin "-") (pinfunction "-_-") (pintype "passive"))
      (node (ref "C44") (pin "2") (pinfunction "2_2") (pintype "passive"))
      (node (ref "C45") (pin "1") (pinfunction "1_1") (pintype "passive"))
      (node (ref "C46") (pin "2") (pinfunction "2_2") (pintype "passive"))
      (node (ref "C5") (pin "-") (pinfunction "-_-") (pintype "passive"))
      (node (ref "C6") (pin "2") (pinfunction "2_2") (pintype "passive"))
      (node (ref "C7") (pin "-") (pinfunction "-_-") (pintype "passive"))
      (node (ref "CONNECTOR_LIPO") (pin "1") (pinfunction "1_1") (pintype "passive"))
      (node (ref "EXT_LOW") (pin "9") (pinfunction "9_9") (pintype "passive"))
      (node (ref "GYRO_LEFT") (pin "5") (pinfunction "5_5") (pintype "passive"))
      (node (ref "GYRO_RIGHT") (pin "5") (pinfunction "5_5") (pintype "passive"))
      (node (ref "IC1") (pin "22") (pinfunction "GND_22") (pintype "power_in"))
      (node (ref "IC1") (pin "8") (pinfunction "GND_8") (pintype "power_in"))
      (node (ref "IC11") (pin "22") (pinfunction "GND_22") (pintype "power_in"))
      (node (ref "IC11") (pin "53") (pinfunction "GND_53") (pintype "power_in"))
      (node (ref "IC11") (pin "63") (pinfunction "GND_63") (pintype "power_in"))
      (node (ref "IC2") (pin "4") (pinfunction "V-_4") (pintype "power_in"))
      (node (ref "IC2") (pin "5") (pinfunction "+IN_5") (pintype "input"))
      (node (ref "IC4") (pin "4") (pinfunction "V-_4") (pintype "power_in"))
      (node (ref "IC4") (pin "5") (pinfunction "+IN_5") (pintype "input"))
      (node (ref "IC5") (pin "4") (pinfunction "V-_4") (pintype "power_in"))
      (node (ref "IC5") (pin "5") (pinfunction "+IN_5") (pintype "input"))
      (node (ref "IC6") (pin "4") (pinfunction "V-_4") (pintype "power_in"))
      (node (ref "IC6") (pin "5") (pinfunction "+IN_5") (pintype "input"))
      (node (ref "IC9") (pin "7") (pinfunction "GND_7") (pintype "power_in"))
      (node (ref "JTAG") (pin "10") (pinfunction "10_10") (pintype "passive"))
      (node (ref "JTAG") (pin "2") (pinfunction "2_2") (pintype "passive"))
      (node (ref "MTC1") (pin "3") (pinfunction "3_3") (pintype "passive"))
      (node (ref "MTC2") (pin "3") (pinfunction "3_3") (pintype "passive"))
      (node (ref "MTC3") (pin "3") (pinfunction "3_3") (pintype "passive"))
      (node (ref "MTC4") (pin "3") (pinfunction "3_3") (pintype "passive"))
      (node (ref "PROG_ISP") (pin "10") (pinfunction "10_10") (pintype "passive"))
      (node (ref "PROG_ISP") (pin "4") (pinfunction "4_4") (pintype "passive"))
      (node (ref "PROG_ISP") (pin "6") (pinfunction "6_6") (pintype "passive"))
      (node (ref "PROG_ISP") (pin "8") (pinfunction "8_8") (pintype "passive"))
      (node (ref "R1") (pin "1") (pinfunction "1_1") (pintype "passive"))
      (node (ref "R13") (pin "1") (pinfunction "1_1") (pintype "passive"))
      (node (ref "R16") (pin "1") (pinfunction "1_1") (pintype "passive"))
      (node (ref "R18") (pin "2") (pinfunction "2_2") (pintype "passive"))
      (node (ref "R30") (pin "2") (pinfunction "2_2") (pintype "passive"))
      (node (ref "R31") (pin "1") (pinfunction "1_1") (pintype "passive"))
      (node (ref "R32") (pin "1") (pinfunction "1_1") (pintype "passive"))
      (node (ref "R33") (pin "2") (pinfunction "2_2") (pintype "passive"))
      (node (ref "R35") (pin "1") (pinfunction "1_1") (pintype "passive"))
      (node (ref "R37") (pin "2") (pinfunction "2_2") (pintype "passive"))
      (node (ref "R38") (pin "2") (pinfunction "2_2") (pintype "passive"))
      (node (ref "R39") (pin "2") (pinfunction "2_2") (pintype "passive"))
      (node (ref "R40") (pin "2") (pinfunction "2_2") (pintype "passive"))
      (node (ref "S2") (pin "1") (pinfunction "1_1") (pintype "passive"))
      (node (ref "S2") (pin "2") (pinfunction "2_2") (pintype "passive"))
      (node (ref "S2") (pin "3") (pinfunction "3_3") (pintype "passive"))
      (node (ref "S2") (pin "4") (pinfunction "4_4") (pintype "passive"))
      (node (ref "S3") (pin "3") (pinfunction "P_3") (pintype "passive"))
      (node (ref "S3") (pin "4") (pinfunction "P1_4") (pintype "passive"))
      (node (ref "SPI_ADDITIONAL") (pin "5") (pinfunction "5_5") (pintype "passive"))
      (node (ref "WII_MOTION") (pin "5") (pinfunction "5_5") (pintype "passive"))
      (node (ref "XBEE1-10") (pin "10") (pinfunction "10_10") (pintype "passive"))
      (node (ref "XBEE_IO") (pin "8") (pinfunction "8_8") (pintype "passive"))
    )
    (net (code "37") (name "Net-(C5-Pad+)") (class "Default")
      (node (ref "C5") (pin "+") (pinfunction "+_+") (pintype "passive"))
      (node (ref "R4") (pin "2") (pinfunction "2_2") (pintype "passive"))
    )
    (net (code "38") (name "Net-(C10-Pad+)") (class "Default")
      (node (ref "C10") (pin "+") (pinfunction "+_+") (pintype "passive"))
      (node (ref "R10") (pin "2") (pinfunction "2_2") (pintype "passive"))
    )
    (net (code "39") (name "Net-(C11-Pad+)") (class "Default")
      (node (ref "C11") (pin "+") (pinfunction "+_+") (pintype "passive"))
      (node (ref "R11") (pin "2") (pinfunction "2_2") (pintype "passive"))
    )
    (net (code "40") (name "Net-(C26-Pad1)") (class "Default")
      (node (ref "C26") (pin "1") (pinfunction "1_1") (pintype "passive"))
      (node (ref "L2") (pin "1") (pinfunction "1_1") (pintype "passive"))
      (node (ref "XBEE11-20") (pin "7") (pinfunction "7_7") (pintype "passive"))
    )
    (net (code "41") (name "Net-(CONNECTOR_LIPO-Pad2)") (class "Default")
      (node (ref "CONNECTOR_LIPO") (pin "2") (pinfunction "2_2") (pintype "passive"))
      (node (ref "R29") (pin "1") (pinfunction "1_1") (pintype "passive"))
    )
    (net (code "42") (name "Net-(CONNECTOR_LIPO-Pad3)") (class "Default")
      (node (ref "CONNECTOR_LIPO") (pin "3") (pinfunction "3_3") (pintype "passive"))
      (node (ref "R28") (pin "1") (pinfunction "1_1") (pintype "passive"))
    )
    (net (code "43") (name "Net-(CONNECTOR_LIPO-Pad4)") (class "Default")
      (node (ref "CONNECTOR_LIPO") (pin "4") (pinfunction "4_4") (pintype "passive"))
      (node (ref "R15") (pin "1") (pinfunction "1_1") (pintype "passive"))
    )
    (net (code "44") (name "Net-(IC1-AREF)") (class "Default")
      (node (ref "C22") (pin "1") (pinfunction "1_1") (pintype "passive"))
      (node (ref "IC1") (pin "21") (pinfunction "AREF_21") (pintype "passive"))
    )
    (net (code "45") (name "Net-(IC1-AVCC)") (class "Default")
      (node (ref "C23") (pin "1") (pinfunction "1_1") (pintype "passive"))
      (node (ref "IC1") (pin "20") (pinfunction "AVCC_20") (pintype "power_in"))
      (node (ref "L4") (pin "1") (pinfunction "1_1") (pintype "passive"))
    )
    (net (code "46") (name "Net-(IC1-PB1(OC1A))") (class "Default")
      (node (ref "IC1") (pin "15") (pinfunction "PB1(OC1A)_15") (pintype "bidirectional"))
      (node (ref "LED6") (pin "A") (pinfunction "A_A") (pintype "passive"))
    )
    (net (code "47") (name "Net-(IC1-PD0(RXD))") (class "Default")
      (node (ref "CONNECTOR_PORTD") (pin "1") (pinfunction "1_1") (pintype "passive"))
      (node (ref "IC1") (pin "2") (pinfunction "PD0(RXD)_2") (pintype "bidirectional"))
    )
    (net (code "48") (name "Net-(IC1-PD1(TXD))") (class "Default")
      (node (ref "CONNECTOR_PORTD") (pin "2") (pinfunction "2_2") (pintype "passive"))
      (node (ref "IC1") (pin "3") (pinfunction "PD1(TXD)_3") (pintype "bidirectional"))
    )
    (net (code "49") (name "Net-(IC1-PD2(INT0))") (class "Default")
      (node (ref "CONNECTOR_PORTD") (pin "3") (pinfunction "3_3") (pintype "passive"))
      (node (ref "IC1") (pin "4") (pinfunction "PD2(INT0)_4") (pintype "bidirectional"))
    )
    (net (code "50") (name "Net-(IC1-PD3(INT1))") (class "Default")
      (node (ref "CONNECTOR_PORTD") (pin "4") (pinfunction "4_4") (pintype "passive"))
      (node (ref "IC1") (pin "5") (pinfunction "PD3(INT1)_5") (pintype "bidirectional"))
    )
    (net (code "51") (name "Net-(IC1-PD4(XCK{slash}T0))") (class "Default")
      (node (ref "CONNECTOR_PORTD") (pin "5") (pinfunction "5_5") (pintype "passive"))
      (node (ref "IC1") (pin "6") (pinfunction "PD4(XCK/T0)_6") (pintype "bidirectional"))
    )
    (net (code "52") (name "Net-(IC1-PD5(T1))") (class "Default")
      (node (ref "CONNECTOR_PORTD") (pin "6") (pinfunction "6_6") (pintype "passive"))
      (node (ref "IC1") (pin "11") (pinfunction "PD5(T1)_11") (pintype "bidirectional"))
    )
    (net (code "53") (name "Net-(IC1-PD6(AIN0))") (class "Default")
      (node (ref "CONNECTOR_PORTD") (pin "7") (pinfunction "7_7") (pintype "passive"))
      (node (ref "IC1") (pin "12") (pinfunction "PD6(AIN0)_12") (pintype "bidirectional"))
    )
    (net (code "54") (name "Net-(IC1-PD7(AIN1))") (class "Default")
      (node (ref "CONNECTOR_PORTD") (pin "8") (pinfunction "8_8") (pintype "passive"))
      (node (ref "IC1") (pin "13") (pinfunction "PD7(AIN1)_13") (pintype "bidirectional"))
    )
    (net (code "55") (name "Net-(IC2A-+IN)") (class "Default")
      (node (ref "C2") (pin "+") (pinfunction "+_+") (pintype "passive"))
      (node (ref "IC2") (pin "3") (pinfunction "+IN_3") (pintype "input"))
      (node (ref "R1") (pin "2") (pinfunction "2_2") (pintype "passive"))
      (node (ref "R2") (pin "2") (pinfunction "2_2") (pintype "passive"))
    )
    (net (code "56") (name "Net-(IC2B--IN)") (class "Default")
      (node (ref "IC2") (pin "6") (pinfunction "-IN_6") (pintype "input"))
      (node (ref "IC2") (pin "7") (pinfunction "OUT_7") (pintype "output"))
    )
    (net (code "57") (name "Net-(IC3-ADJ)") (class "Default")
      (node (ref "C17") (pin "+") (pinfunction "+_+") (pintype "passive"))
      (node (ref "IC3") (pin "1") (pinfunction "ADJ_1") (pintype "input"))
      (node (ref "R12") (pin "2") (pinfunction "2_2") (pintype "passive"))
      (node (ref "R13") (pin "2") (pinfunction "2_2") (pintype "passive"))
    )
    (net (code "58") (name "Net-(IC4A-+IN)") (class "Default")
      (node (ref "C4") (pin "+") (pinfunction "+_+") (pintype "passive"))
      (node (ref "IC4") (pin "3") (pinfunction "+IN_3") (pintype "input"))
      (node (ref "R3") (pin "1") (pinfunction "1_1") (pintype "passive"))
    )
    (net (code "59") (name "Net-(IC4A--IN)") (class "Default")
      (node (ref "IC4") (pin "2") (pinfunction "-IN_2") (pintype "input"))
      (node (ref "R4") (pin "1") (pinfunction "1_1") (pintype "passive"))
      (node (ref "R5") (pin "2") (pinfunction "2_2") (pintype "passive"))
    )
    (net (code "60") (name "Net-(IC4B--IN)") (class "Default")
      (node (ref "IC4") (pin "6") (pinfunction "-IN_6") (pintype "input"))
      (node (ref "IC4") (pin "7") (pinfunction "OUT_7") (pintype "output"))
    )
    (net (code "61") (name "Net-(IC5A-+IN)") (class "Default")
      (node (ref "C8") (pin "+") (pinfunction "+_+") (pintype "passive"))
      (node (ref "IC5") (pin "3") (pinfunction "+IN_3") (pintype "input"))
      (node (ref "R8") (pin "2") (pinfunction "2_2") (pintype "passive"))
    )
    (net (code "62") (name "Net-(IC5A--IN)") (class "Default")
      (node (ref "IC5") (pin "2") (pinfunction "-IN_2") (pintype "input"))
      (node (ref "R11") (pin "1") (pinfunction "1_1") (pintype "passive"))
      (node (ref "R6") (pin "2") (pinfunction "2_2") (pintype "passive"))
    )
    (net (code "63") (name "Net-(IC5B--IN)") (class "Default")
      (node (ref "IC5") (pin "6") (pinfunction "-IN_6") (pintype "input"))
      (node (ref "IC5") (pin "7") (pinfunction "OUT_7") (pintype "output"))
    )
    (net (code "64") (name "Net-(IC6A-+IN)") (class "Default")
      (node (ref "C9") (pin "+") (pinfunction "+_+") (pintype "passive"))
      (node (ref "IC6") (pin "3") (pinfunction "+IN_3") (pintype "input"))
      (node (ref "R9") (pin "2") (pinfunction "2_2") (pintype "passive"))
    )
    (net (code "65") (name "Net-(IC6A--IN)") (class "Default")
      (node (ref "IC6") (pin "2") (pinfunction "-IN_2") (pintype "input"))
      (node (ref "R10") (pin "1") (pinfunction "1_1") (pintype "passive"))
      (node (ref "R7") (pin "2") (pinfunction "2_2") (pintype "passive"))
    )
    (net (code "66") (name "Net-(IC6B--IN)") (class "Default")
      (node (ref "IC6") (pin "6") (pinfunction "-IN_6") (pintype "input"))
      (node (ref "IC6") (pin "7") (pinfunction "OUT_7") (pintype "output"))
    )
    (net (code "67") (name "Net-(IC9A-I0)") (class "Default")
      (node (ref "C33") (pin "1") (pinfunction "1_1") (pintype "passive"))
      (node (ref "IC9") (pin "1") (pinfunction "I0_1") (pintype "input"))
      (node (ref "R24") (pin "1") (pinfunction "1_1") (pintype "passive"))
    )
    (net (code "68") (name "Net-(IC9B-I0)") (class "Default")
      (node (ref "C34") (pin "1") (pinfunction "1_1") (pintype "passive"))
      (node (ref "IC9") (pin "4") (pinfunction "I0_4") (pintype "input"))
      (node (ref "R25") (pin "1") (pinfunction "1_1") (pintype "passive"))
    )
    (net (code "69") (name "Net-(IC9C-I0)") (class "Default")
      (node (ref "C35") (pin "1") (pinfunction "1_1") (pintype "passive"))
      (node (ref "IC9") (pin "9") (pinfunction "I0_9") (pintype "input"))
      (node (ref "R26") (pin "1") (pinfunction "1_1") (pintype "passive"))
    )
    (net (code "70") (name "Net-(IC9D-I0)") (class "Default")
      (node (ref "C36") (pin "1") (pinfunction "1_1") (pintype "passive"))
      (node (ref "IC9") (pin "12") (pinfunction "I0_12") (pintype "input"))
      (node (ref "R27") (pin "1") (pinfunction "1_1") (pintype "passive"))
    )
    (net (code "71") (name "Net-(IC11-(A8)PC0)") (class "Default")
      (node (ref "EXT_HIGH") (pin "1") (pinfunction "1_1") (pintype "passive"))
      (node (ref "IC11") (pin "35") (pinfunction "(A8)PC0_35") (pintype "output"))
    )
    (net (code "72") (name "Net-(IC11-(A9)PC1)") (class "Default")
      (node (ref "EXT_HIGH") (pin "2") (pinfunction "2_2") (pintype "passive"))
      (node (ref "IC11") (pin "36") (pinfunction "(A9)PC1_36") (pintype "output"))
    )
    (net (code "73") (name "Net-(IC11-(A10)PC2)") (class "Default")
      (node (ref "EXT_HIGH") (pin "3") (pinfunction "3_3") (pintype "passive"))
      (node (ref "IC11") (pin "37") (pinfunction "(A10)PC2_37") (pintype "output"))
    )
    (net (code "74") (name "Net-(IC11-(A11)PC3)") (class "Default")
      (node (ref "EXT_HIGH") (pin "4") (pinfunction "4_4") (pintype "passive"))
      (node (ref "IC11") (pin "38") (pinfunction "(A11)PC3_38") (pintype "output"))
    )
    (net (code "75") (name "Net-(IC11-(A12)PC4)") (class "Default")
      (node (ref "EXT_HIGH") (pin "5") (pinfunction "5_5") (pintype "passive"))
      (node (ref "IC11") (pin "39") (pinfunction "(A12)PC4_39") (pintype "output"))
    )
    (net (code "76") (name "Net-(IC11-(A13)PC5)") (class "Default")
      (node (ref "EXT_HIGH") (pin "6") (pinfunction "6_6") (pintype "passive"))
      (node (ref "IC11") (pin "40") (pinfunction "(A13)PC5_40") (pintype "output"))
    )
    (net (code "77") (name "Net-(IC11-(A14)PC6)") (class "Default")
      (node (ref "EXT_HIGH") (pin "7") (pinfunction "7_7") (pintype "passive"))
      (node (ref "IC11") (pin "41") (pinfunction "(A14)PC6_41") (pintype "output"))
    )
    (net (code "78") (name "Net-(IC11-(A15)PC7)") (class "Default")
      (node (ref "EXT_HIGH") (pin "8") (pinfunction "8_8") (pintype "passive"))
      (node (ref "IC11") (pin "42") (pinfunction "(A15)PC7_42") (pintype "output"))
    )
    (net (code "79") (name "Net-(IC11-(AD0)PA0)") (class "Default")
      (node (ref "EXT_LOW") (pin "1") (pinfunction "1_1") (pintype "passive"))
      (node (ref "IC11") (pin "51") (pinfunction "(AD0)PA0_51") (pintype "bidirectional"))
    )
    (net (code "80") (name "Net-(IC11-(AD1)PA1)") (class "Default")
      (node (ref "EXT_LOW") (pin "2") (pinfunction "2_2") (pintype "passive"))
      (node (ref "IC11") (pin "50") (pinfunction "(AD1)PA1_50") (pintype "bidirectional"))
    )
    (net (code "81") (name "Net-(IC11-(AD2)PA2)") (class "Default")
      (node (ref "EXT_LOW") (pin "3") (pinfunction "3_3") (pintype "passive"))
      (node (ref "IC11") (pin "49") (pinfunction "(AD2)PA2_49") (pintype "bidirectional"))
    )
    (net (code "82") (name "Net-(IC11-(AD3)PA3)") (class "Default")
      (node (ref "EXT_LOW") (pin "4") (pinfunction "4_4") (pintype "passive"))
      (node (ref "IC11") (pin "48") (pinfunction "(AD3)PA3_48") (pintype "bidirectional"))
    )
    (net (code "83") (name "Net-(IC11-(AD4)PA4)") (class "Default")
      (node (ref "EXT_LOW") (pin "5") (pinfunction "5_5") (pintype "passive"))
      (node (ref "IC11") (pin "47") (pinfunction "(AD4)PA4_47") (pintype "bidirectional"))
    )
    (net (code "84") (name "Net-(IC11-(AD5)PA5)") (class "Default")
      (node (ref "EXT_LOW") (pin "6") (pinfunction "6_6") (pintype "passive"))
      (node (ref "IC11") (pin "46") (pinfunction "(AD5)PA5_46") (pintype "bidirectional"))
    )
    (net (code "85") (name "Net-(IC11-(AD6)PA6)") (class "Default")
      (node (ref "EXT_LOW") (pin "7") (pinfunction "7_7") (pintype "passive"))
      (node (ref "IC11") (pin "45") (pinfunction "(AD6)PA6_45") (pintype "bidirectional"))
    )
    (net (code "86") (name "Net-(IC11-(AD7)PA7)") (class "Default")
      (node (ref "EXT_LOW") (pin "8") (pinfunction "8_8") (pintype "passive"))
      (node (ref "IC11") (pin "44") (pinfunction "(AD7)PA7_44") (pintype "bidirectional"))
    )
    (net (code "87") (name "Net-(IC11-(OC0)PB4)") (class "Default")
      (node (ref "IC11") (pin "14") (pinfunction "(OC0)PB4_14") (pintype "bidirectional"))
      (node (ref "LED3") (pin "A") (pinfunction "A_A") (pintype "passive"))
    )
    (net (code "88") (name "Net-(IC11-(OC1A)PB5)") (class "Default")
      (node (ref "IC11") (pin "15") (pinfunction "(OC1A)PB5_15") (pintype "bidirectional"))
      (node (ref "MTC1") (pin "1") (pinfunction "1_1") (pintype "passive"))
    )
    (net (code "89") (name "Net-(IC11-(OC1B)PB6)") (class "Default")
      (node (ref "IC11") (pin "16") (pinfunction "(OC1B)PB6_16") (pintype "bidirectional"))
      (node (ref "MTC2") (pin "1") (pinfunction "1_1") (pintype "passive"))
    )
    (net (code "90") (name "Net-(IC11-(OC2{slash}OC1C)PB7)") (class "Default")
      (node (ref "IC11") (pin "17") (pinfunction "(OC2/OC1C)PB7_17") (pintype "bidirectional"))
      (node (ref "MTC3") (pin "1") (pinfunction "1_1") (pintype "passive"))
    )
    (net (code "91") (name "Net-(IC11-(OC3A{slash}AIN1)PE3)") (class "Default")
      (node (ref "IC11") (pin "5") (pinfunction "(OC3A/AIN1)PE3_5") (pintype "bidirectional"))
      (node (ref "LED4") (pin "A") (pinfunction "A_A") (pintype "passive"))
    )
    (net (code "92") (name "Net-(IC11-(OC3B{slash}INT4)PE4)") (class "Default")
      (node (ref "IC11") (pin "6") (pinfunction "(OC3B/INT4)PE4_6") (pintype "bidirectional"))
      (node (ref "LED5") (pin "A") (pinfunction "A_A") (pintype "passive"))
    )
    (net (code "93") (name "Net-(IC11-(OC3C{slash}INT5)PE5)") (class "Default")
      (node (ref "IC11") (pin "7") (pinfunction "(OC3C/INT5)PE5_7") (pintype "bidirectional"))
      (node (ref "MTC4") (pin "1") (pinfunction "1_1") (pintype "passive"))
    )
    (net (code "94") (name "Net-(IC11-AREF)") (class "Default")
      (node (ref "C45") (pin "2") (pinfunction "2_2") (pintype "passive"))
      (node (ref "IC11") (pin "62") (pinfunction "AREF_62") (pintype "passive"))
    )
    (net (code "95") (name "Net-(IC11-AVCC)") (class "Default")
      (node (ref "C46") (pin "1") (pinfunction "1_1") (pintype "passive"))
      (node (ref "IC11") (pin "64") (pinfunction "AVCC_64") (pintype "power_in"))
      (node (ref "L1") (pin "1") (pinfunction "1_1") (pintype "passive"))
    )
    (net (code "96") (name "Net-(IC11-PF0(ADC0))") (class "Default")
      (node (ref "IC11") (pin "61") (pinfunction "PF0(ADC0)_61") (pintype "input"))
      (node (ref "R15") (pin "2") (pinfunction "2_2") (pintype "passive"))
      (node (ref "R16") (pin "2") (pinfunction "2_2") (pintype "passive"))
    )
    (net (code "97") (name "Net-(IC11-PF1(ADC1))") (class "Default")
      (node (ref "IC11") (pin "60") (pinfunction "PF1(ADC1)_60") (pintype "input"))
      (node (ref "R28") (pin "2") (pinfunction "2_2") (pintype "passive"))
      (node (ref "R31") (pin "2") (pinfunction "2_2") (pintype "passive"))
    )
    (net (code "98") (name "Net-(IC11-PF2(ADC2))") (class "Default")
      (node (ref "IC11") (pin "59") (pinfunction "PF2(ADC2)_59") (pintype "input"))
      (node (ref "R29") (pin "2") (pinfunction "2_2") (pintype "passive"))
      (node (ref "R32") (pin "2") (pinfunction "2_2") (pintype "passive"))
    )
    (net (code "99") (name "Net-(IC11-PF4(ADC4{slash}TCK))") (class "Default")
      (node (ref "IC11") (pin "57") (pinfunction "PF4(ADC4/TCK)_57") (pintype "input"))
      (node (ref "JTAG") (pin "1") (pinfunction "1_1") (pintype "passive"))
    )
    (net (code "100") (name "Net-(IC11-PF5(ADC5{slash}TMS))") (class "Default")
      (node (ref "IC11") (pin "56") (pinfunction "PF5(ADC5/TMS)_56") (pintype "input"))
      (node (ref "JTAG") (pin "5") (pinfunction "5_5") (pintype "passive"))
    )
    (net (code "101") (name "Net-(IC11-PF6(ADC6{slash}TDO))") (class "Default")
      (node (ref "IC11") (pin "55") (pinfunction "PF6(ADC6/TDO)_55") (pintype "input"))
      (node (ref "JTAG") (pin "3") (pinfunction "3_3") (pintype "passive"))
    )
    (net (code "102") (name "Net-(IC11-PF7(ADC7{slash}TDI))") (class "Default")
      (node (ref "IC11") (pin "54") (pinfunction "PF7(ADC7/TDI)_54") (pintype "input"))
      (node (ref "JTAG") (pin "9") (pinfunction "9_9") (pintype "passive"))
    )
    (net (code "103") (name "Net-(IC11-PG3(TOSC2))") (class "Default")
      (node (ref "IC11") (pin "18") (pinfunction "PG3(TOSC2)_18") (pintype "bidirectional"))
      (node (ref "XBEE1-10") (pin "9") (pinfunction "9_9") (pintype "passive"))
    )
    (net (code "104") (name "Net-(IC11-PG4(TOSC1))") (class "Default")
      (node (ref "IC11") (pin "19") (pinfunction "PG4(TOSC1)_19") (pintype "bidirectional"))
      (node (ref "XBEE11-20") (pin "8") (pinfunction "8_8") (pintype "passive"))
    )
    (net (code "105") (name "Net-(IC11-XTAL1)") (class "Default")
      (node (ref "C42") (pin "1") (pinfunction "1_1") (pintype "passive"))
      (node (ref "IC11") (pin "24") (pinfunction "XTAL1_24") (pintype "bidirectional"))
      (node (ref "Q1") (pin "2") (pinfunction "2_2") (pintype "passive"))
    )
    (net (code "106") (name "Net-(IC11-XTAL2)") (class "Default")
      (node (ref "C41") (pin "1") (pinfunction "1_1") (pintype "passive"))
      (node (ref "IC11") (pin "23") (pinfunction "XTAL2_23") (pintype "bidirectional"))
      (node (ref "Q1") (pin "1") (pinfunction "1_1") (pintype "passive"))
    )
    (net (code "107") (name "Net-(LED1-PadA)") (class "Default")
      (node (ref "LED1") (pin "A") (pinfunction "A_A") (pintype "passive"))
      (node (ref "XBEE1-10") (pin "6") (pinfunction "6_6") (pintype "passive"))
    )
    (net (code "108") (name "Net-(LED1-PadC)") (class "Default")
      (node (ref "LED1") (pin "C") (pinfunction "C_C") (pintype "passive"))
      (node (ref "R18") (pin "1") (pinfunction "1_1") (pintype "passive"))
    )
    (net (code "109") (name "Net-(LED2-PadA)") (class "Default")
      (node (ref "LED2") (pin "A") (pinfunction "A_A") (pintype "passive"))
      (node (ref "XBEE1-10") (pin "7") (pinfunction "7_7") (pintype "passive"))
    )
    (net (code "110") (name "Net-(LED2-PadC)") (class "Default")
      (node (ref "LED2") (pin "C") (pinfunction "C_C") (pintype "passive"))
      (node (ref "R30") (pin "1") (pinfunction "1_1") (pintype "passive"))
    )
    (net (code "111") (name "Net-(LED3-PadC)") (class "Default")
      (node (ref "LED3") (pin "C") (pinfunction "C_C") (pintype "passive"))
      (node (ref "R33") (pin "1") (pinfunction "1_1") (pintype "passive"))
    )
    (net (code "112") (name "Net-(LED4-PadC)") (class "Default")
      (node (ref "LED4") (pin "C") (pinfunction "C_C") (pintype "passive"))
      (node (ref "R38") (pin "1") (pinfunction "1_1") (pintype "passive"))
    )
    (net (code "113") (name "Net-(LED5-PadC)") (class "Default")
      (node (ref "LED5") (pin "C") (pinfunction "C_C") (pintype "passive"))
      (node (ref "R39") (pin "1") (pinfunction "1_1") (pintype "passive"))
    )
    (net (code "114") (name "Net-(LED6-PadC)") (class "Default")
      (node (ref "LED6") (pin "C") (pinfunction "C_C") (pintype "passive"))
      (node (ref "R40") (pin "1") (pinfunction "1_1") (pintype "passive"))
    )
    (net (code "115") (name "Net-(R19-Pad1)") (class "Default")
      (node (ref "R19") (pin "1") (pinfunction "1_1") (pintype "passive"))
      (node (ref "R24") (pin "2") (pinfunction "2_2") (pintype "passive"))
      (node (ref "S2") (pin "8") (pinfunction "8_8") (pintype "passive"))
    )
    (net (code "116") (name "Net-(R20-Pad1)") (class "Default")
      (node (ref "R20") (pin "1") (pinfunction "1_1") (pintype "passive"))
      (node (ref "R25") (pin "2") (pinfunction "2_2") (pintype "passive"))
      (node (ref "S2") (pin "7") (pinfunction "7_7") (pintype "passive"))
    )
    (net (code "117") (name "Net-(R21-Pad1)") (class "Default")
      (node (ref "R21") (pin "1") (pinfunction "1_1") (pintype "passive"))
      (node (ref "R26") (pin "2") (pinfunction "2_2") (pintype "passive"))
      (node (ref "S2") (pin "6") (pinfunction "6_6") (pintype "passive"))
    )
    (net (code "118") (name "Net-(R22-Pad1)") (class "Default")
      (node (ref "R22") (pin "1") (pinfunction "1_1") (pintype "passive"))
      (node (ref "R27") (pin "2") (pinfunction "2_2") (pintype "passive"))
      (node (ref "S2") (pin "5") (pinfunction "5_5") (pintype "passive"))
    )
    (net (code "119") (name "Net-(R34-Pad1)") (class "Default")
      (node (ref "R34") (pin "1") (pinfunction "1_1") (pintype "passive"))
      (node (ref "R35") (pin "2") (pinfunction "2_2") (pintype "passive"))
      (node (ref "XBEE1-10") (pin "3") (pinfunction "3_3") (pintype "passive"))
    )
    (net (code "120") (name "Net-(R36-Pad2)") (class "Default")
      (node (ref "R36") (pin "2") (pinfunction "2_2") (pintype "passive"))
      (node (ref "R37") (pin "1") (pinfunction "1_1") (pintype "passive"))
      (node (ref "XBEE11-20") (pin "5") (pinfunction "5_5") (pintype "passive"))
    )
    (net (code "121") (name "Net-(S3-S)") (class "Default")
      (node (ref "S3") (pin "1") (pinfunction "S_1") (pintype "passive"))
      (node (ref "S3") (pin "2") (pinfunction "S1_2") (pintype "passive"))
      (node (ref "XBEE1-10") (pin "5") (pinfunction "5_5") (pintype "passive"))
    )
    (net (code "122") (name "Net-(XBEE1-10-Pad4)") (class "Default")
      (node (ref "XBEE1-10") (pin "4") (pinfunction "4_4") (pintype "passive"))
      (node (ref "XBEE_IO") (pin "6") (pinfunction "6_6") (pintype "passive"))
    )
    (net (code "123") (name "Net-(XBEE11-20-Pad1)") (class "Default")
      (node (ref "XBEE11-20") (pin "1") (pinfunction "1_1") (pintype "passive"))
      (node (ref "XBEE_IO") (pin "1") (pinfunction "1_1") (pintype "passive"))
    )
    (net (code "124") (name "Net-(XBEE11-20-Pad2)") (class "Default")
      (node (ref "XBEE11-20") (pin "2") (pinfunction "2_2") (pintype "passive"))
      (node (ref "XBEE_IO") (pin "2") (pinfunction "2_2") (pintype "passive"))
    )
    (net (code "125") (name "Net-(XBEE11-20-Pad3)") (class "Default")
      (node (ref "XBEE11-20") (pin "3") (pinfunction "3_3") (pintype "passive"))
      (node (ref "XBEE_IO") (pin "3") (pinfunction "3_3") (pintype "passive"))
    )
    (net (code "126") (name "Net-(XBEE11-20-Pad4)") (class "Default")
      (node (ref "XBEE11-20") (pin "4") (pinfunction "4_4") (pintype "passive"))
      (node (ref "XBEE_IO") (pin "4") (pinfunction "4_4") (pintype "passive"))
    )
    (net (code "127") (name "Net-(XBEE11-20-Pad6)") (class "Default")
      (node (ref "XBEE11-20") (pin "6") (pinfunction "6_6") (pintype "passive"))
      (node (ref "XBEE_IO") (pin "7") (pinfunction "7_7") (pintype "passive"))
    )
    (net (code "128") (name "Net-(XBEE11-20-Pad10)") (class "Default")
      (node (ref "XBEE11-20") (pin "10") (pinfunction "10_10") (pintype "passive"))
      (node (ref "XBEE_IO") (pin "5") (pinfunction "5_5") (pintype "passive"))
    )
    (net (code "129") (name "unconnected-(GYRO_LEFT-Pad2)") (class "Default")
      (node (ref "GYRO_LEFT") (pin "2") (pinfunction "2_2") (pintype "passive"))
    )
    (net (code "130") (name "unconnected-(IC1-PB0(ICP)-Pad14)") (class "Default")
      (node (ref "IC1") (pin "14") (pinfunction "PB0(ICP)_14") (pintype "bidirectional"))
    )
    (net (code "131") (name "unconnected-(IC1-PB6(XTAL1{slash}TOSC1)-Pad9)") (class "Default")
      (node (ref "IC1") (pin "9") (pinfunction "PB6(XTAL1/TOSC1)_9") (pintype "bidirectional"))
    )
    (net (code "132") (name "unconnected-(IC1-PB7(XTAL2{slash}TOSC2)-Pad10)") (class "Default")
      (node (ref "IC1") (pin "10") (pinfunction "PB7(XTAL2/TOSC2)_10") (pintype "bidirectional"))
    )
    (net (code "133") (name "unconnected-(IC1-PC3(ADC3)-Pad26)") (class "Default")
      (node (ref "IC1") (pin "26") (pinfunction "PC3(ADC3)_26") (pintype "bidirectional"))
    )
    (net (code "134") (name "unconnected-(IC11-(MOSI)PB2-Pad12)") (class "Default")
      (node (ref "IC11") (pin "12") (pinfunction "(MOSI)PB2_12") (pintype "bidirectional"))
    )
    (net (code "135") (name "unconnected-(IC11-PEN-Pad1)") (class "Default")
      (node (ref "IC11") (pin "1") (pinfunction "PEN_1") (pintype "input"))
    )
    (net (code "136") (name "unconnected-(IC11-PF3(ADC3)-Pad58)") (class "Default")
      (node (ref "IC11") (pin "58") (pinfunction "PF3(ADC3)_58") (pintype "input"))
    )
    (net (code "137") (name "unconnected-(JTAG-Pad8)") (class "Default")
      (node (ref "JTAG") (pin "8") (pinfunction "8_8") (pintype "passive"))
    )
    (net (code "138") (name "unconnected-(MTC1-Pad2)") (class "Default")
      (node (ref "MTC1") (pin "2") (pinfunction "2_2") (pintype "passive"))
    )
    (net (code "139") (name "unconnected-(MTC2-Pad2)") (class "Default")
      (node (ref "MTC2") (pin "2") (pinfunction "2_2") (pintype "passive"))
    )
    (net (code "140") (name "unconnected-(MTC4-Pad2)") (class "Default")
      (node (ref "MTC4") (pin "2") (pinfunction "2_2") (pintype "passive"))
    )
    (net (code "141") (name "unconnected-(PROG_ISP-Pad3)") (class "Default")
      (node (ref "PROG_ISP") (pin "3") (pinfunction "3_3") (pintype "passive"))
    )
    (net (code "142") (name "unconnected-(XBEE1-10-Pad8)") (class "Default")
      (node (ref "XBEE1-10") (pin "8") (pinfunction "8_8") (pintype "passive"))
    )
  )
)
